# SCH_Business-card-2_2024-04-10.net
KiCad netlist of a schematic drawn in EasyEDA
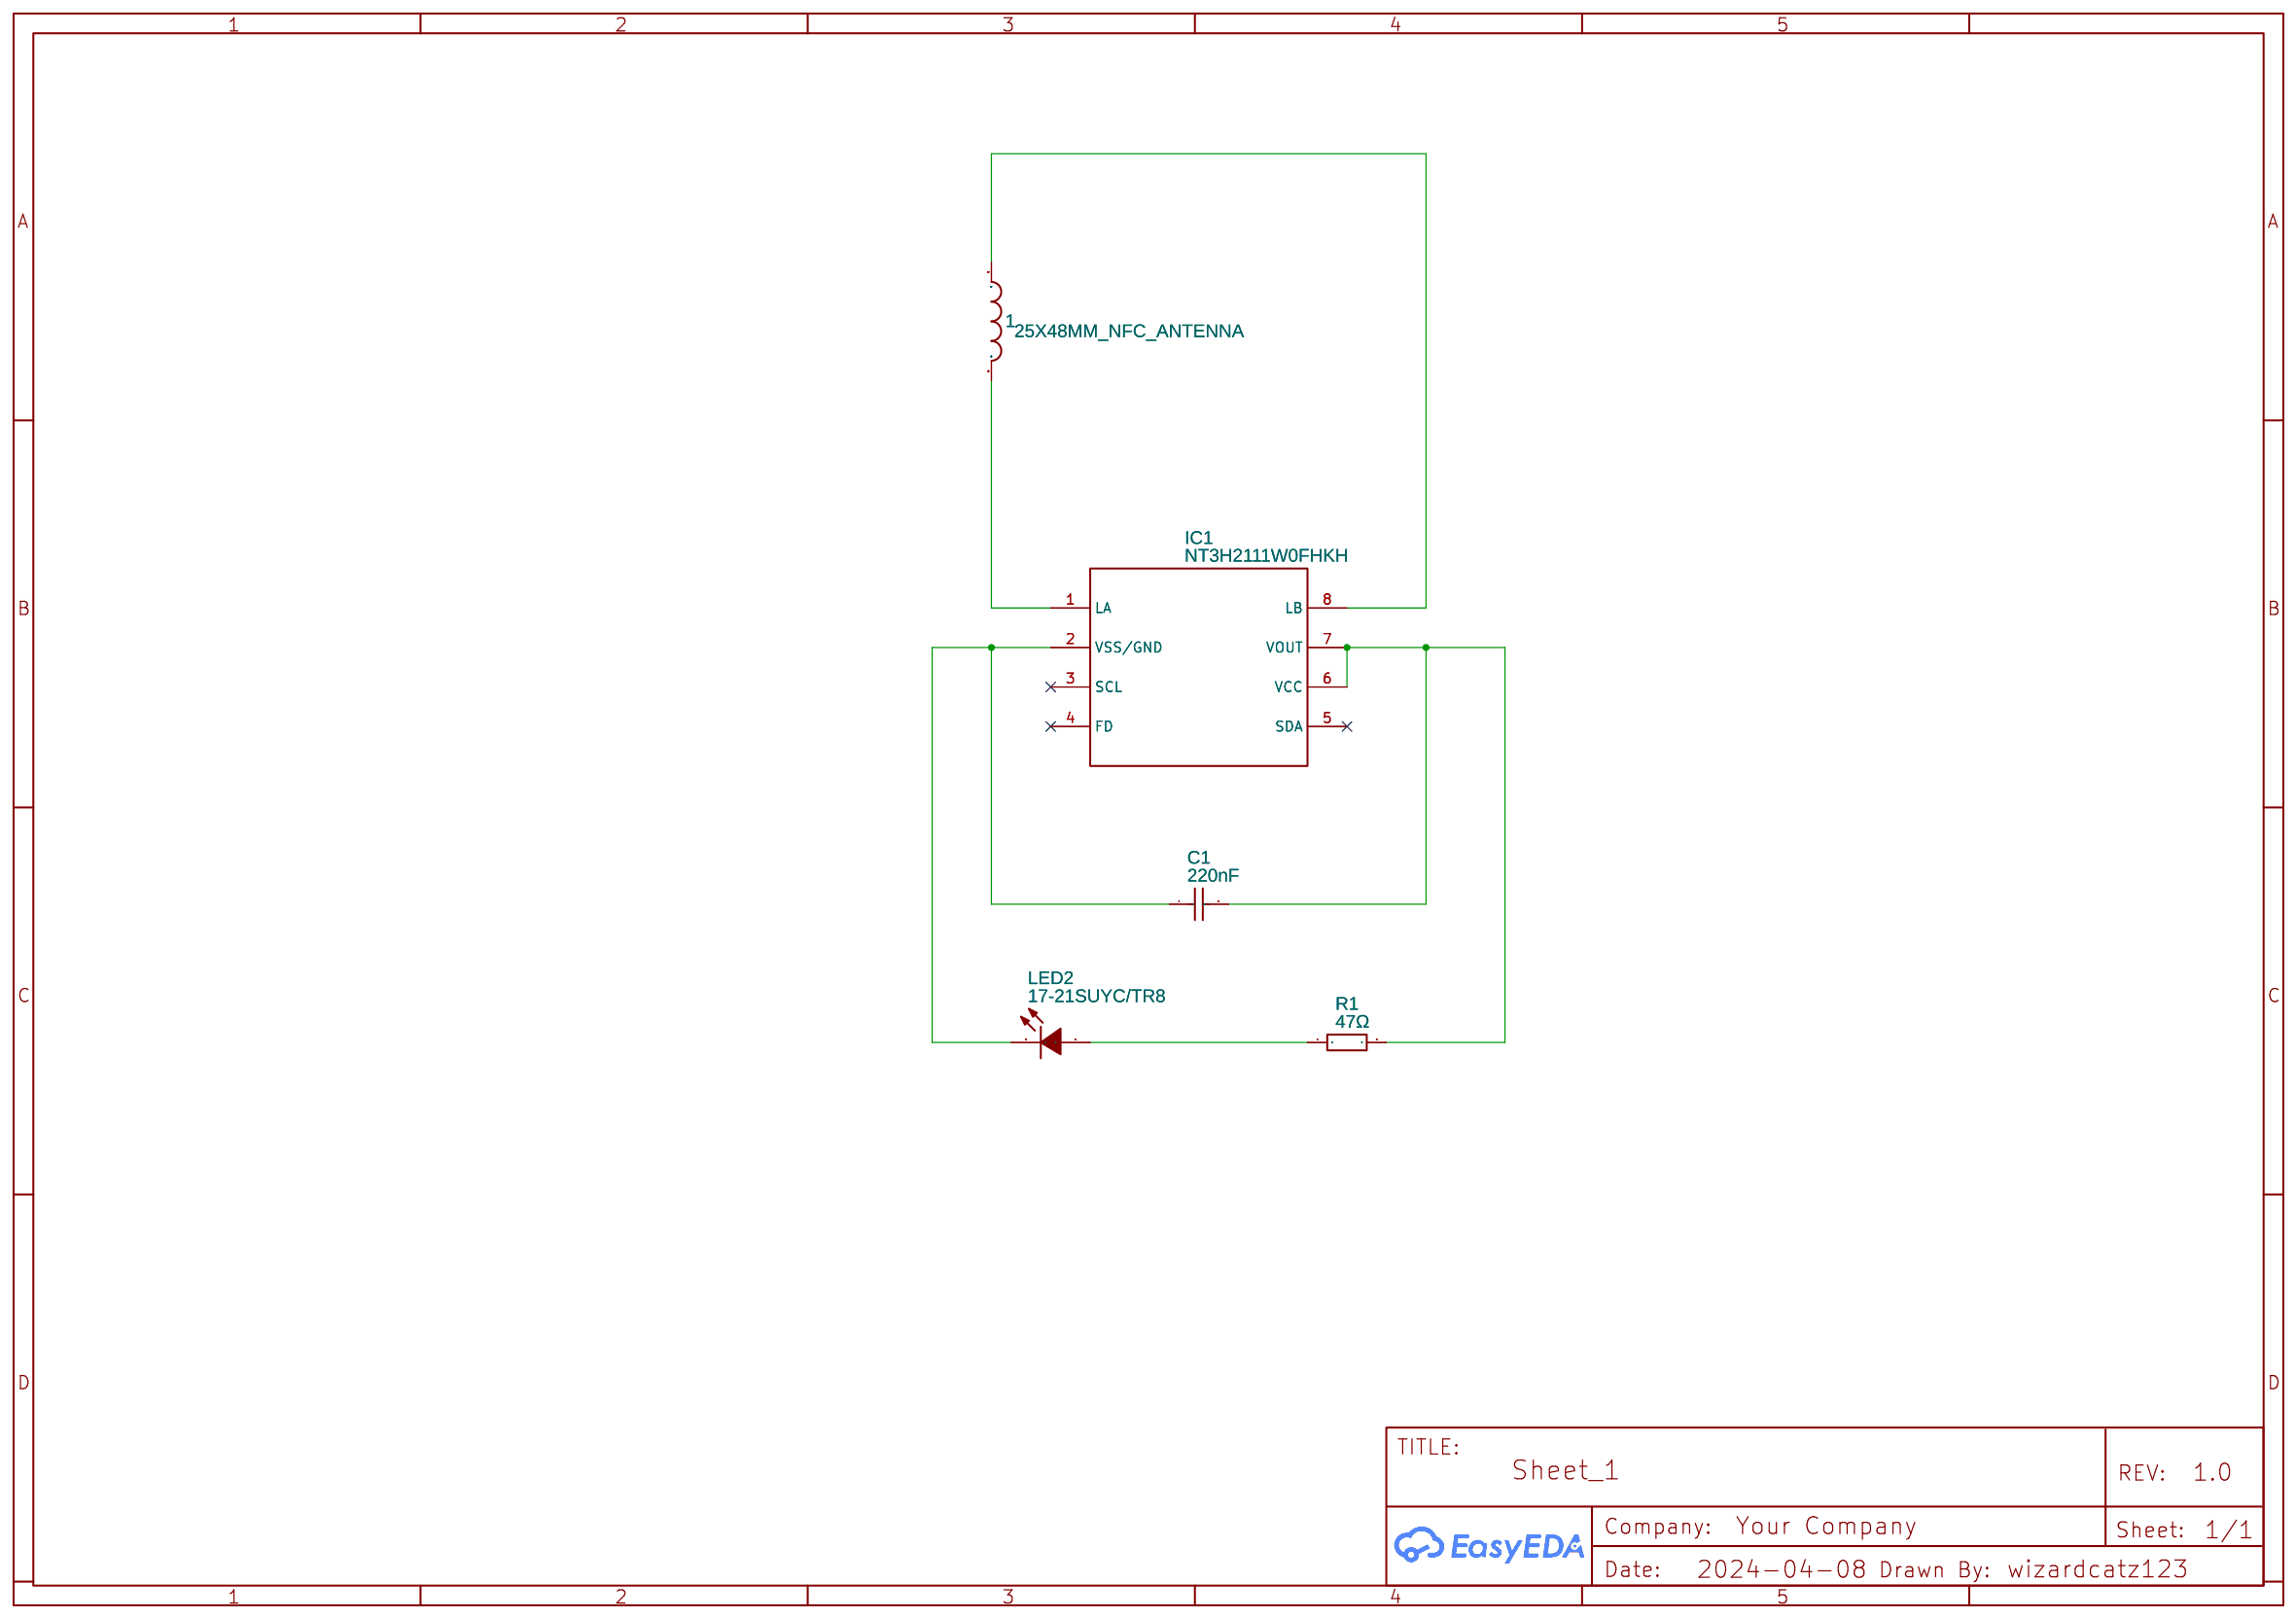
[diagram p0: schematic sheet]

(export (version "E")
  (design (tool "Eeschema 10.0.6"))
  (components
    (comp (ref "1") (value "25X48MM_NFC_ANTENNA") (libsource (lib "") (part "25X48MM_NFC_ANTENNA")))
    (comp (ref "C1")
      (value "220nF")
      (fields (field (name "Manufacturer Part") "CL10B224KA8NNNC") (field (name "Manufacturer") "SAMSUNG"))
      (libsource (lib "") (part "0603C-220nF_CL10B224KA8NNNC"))
    )
    (comp (ref "IC1") (value "NT3H2111W0FHKH") (libsource (lib "") (part "NT3H2111W0FHKH")))
    (comp (ref "LED2")
      (value "17-21SUYC/TR8")
      (fields (field (name "Manufacturer Part") "KT-0805黄灯") (field (name "Manufacturer") "KENTO"))
      (libsource (lib "") (part "17-21SUYC/TR8"))
    )
    (comp (ref "R1")
      (value "47Ω")
      (fields
        (field (name "Manufacturer Part") "0603WAF470JT5E")
        (field (name "Manufacturer") "UNI-ROYAL(厚声)")
      )
      (libsource (lib "") (part "0603WAF470JT5E"))
    )
  )
  (nets
    (net (code "1") (name "Net-(IC1-LA)") (class "Default")
      (node (ref "1") (pin "P$2") (pinfunction "P$2_P$2") (pintype "bidirectional"))
      (node (ref "IC1") (pin "1") (pinfunction "LA_1") (pintype "unspecified"))
    )
    (net (code "2") (name "Net-(IC1-LB)") (class "Default")
      (node (ref "1") (pin "P$1") (pinfunction "P$1_P$1") (pintype "bidirectional"))
      (node (ref "IC1") (pin "8") (pinfunction "LB_8") (pintype "unspecified"))
    )
    (net (code "3") (name "Net-(IC1-VCC)") (class "Default")
      (node (ref "C1") (pin "2") (pinfunction "2_2") (pintype "input"))
      (node (ref "IC1") (pin "6") (pinfunction "VCC_6") (pintype "passive"))
      (node (ref "IC1") (pin "7") (pinfunction "VOUT_7") (pintype "passive"))
      (node (ref "R1") (pin "2") (pinfunction "2_2") (pintype "input"))
    )
    (net (code "4") (name "Net-(IC1-VSS{slash}GND)") (class "Default")
      (node (ref "C1") (pin "1") (pinfunction "1_1") (pintype "input"))
      (node (ref "IC1") (pin "2") (pinfunction "VSS/GND_2") (pintype "unspecified"))
      (node (ref "LED2") (pin "2") (pinfunction "-_2") (pintype "unspecified"))
    )
    (net (code "5") (name "Net-(LED2-+)") (class "Default")
      (node (ref "LED2") (pin "1") (pinfunction "+_1") (pintype "unspecified"))
      (node (ref "R1") (pin "1") (pinfunction "1_1") (pintype "input"))
    )
    (net (code "6") (name "unconnected-(IC1-FD-Pad4)") (class "Default")
      (node (ref "IC1") (pin "4") (pinfunction "FD_4") (pintype "unspecified+no_connect"))
    )
    (net (code "7") (name "unconnected-(IC1-SCL-Pad3)") (class "Default")
      (node (ref "IC1") (pin "3") (pinfunction "SCL_3") (pintype "unspecified+no_connect"))
    )
    (net (code "8") (name "unconnected-(IC1-SDA-Pad5)") (class "Default")
      (node (ref "IC1") (pin "5") (pinfunction "SDA_5") (pintype "unspecified+no_connect"))
    )
  )
)
